# SCH_Controller.net
KiCad netlist of a schematic drawn in Altium Designer
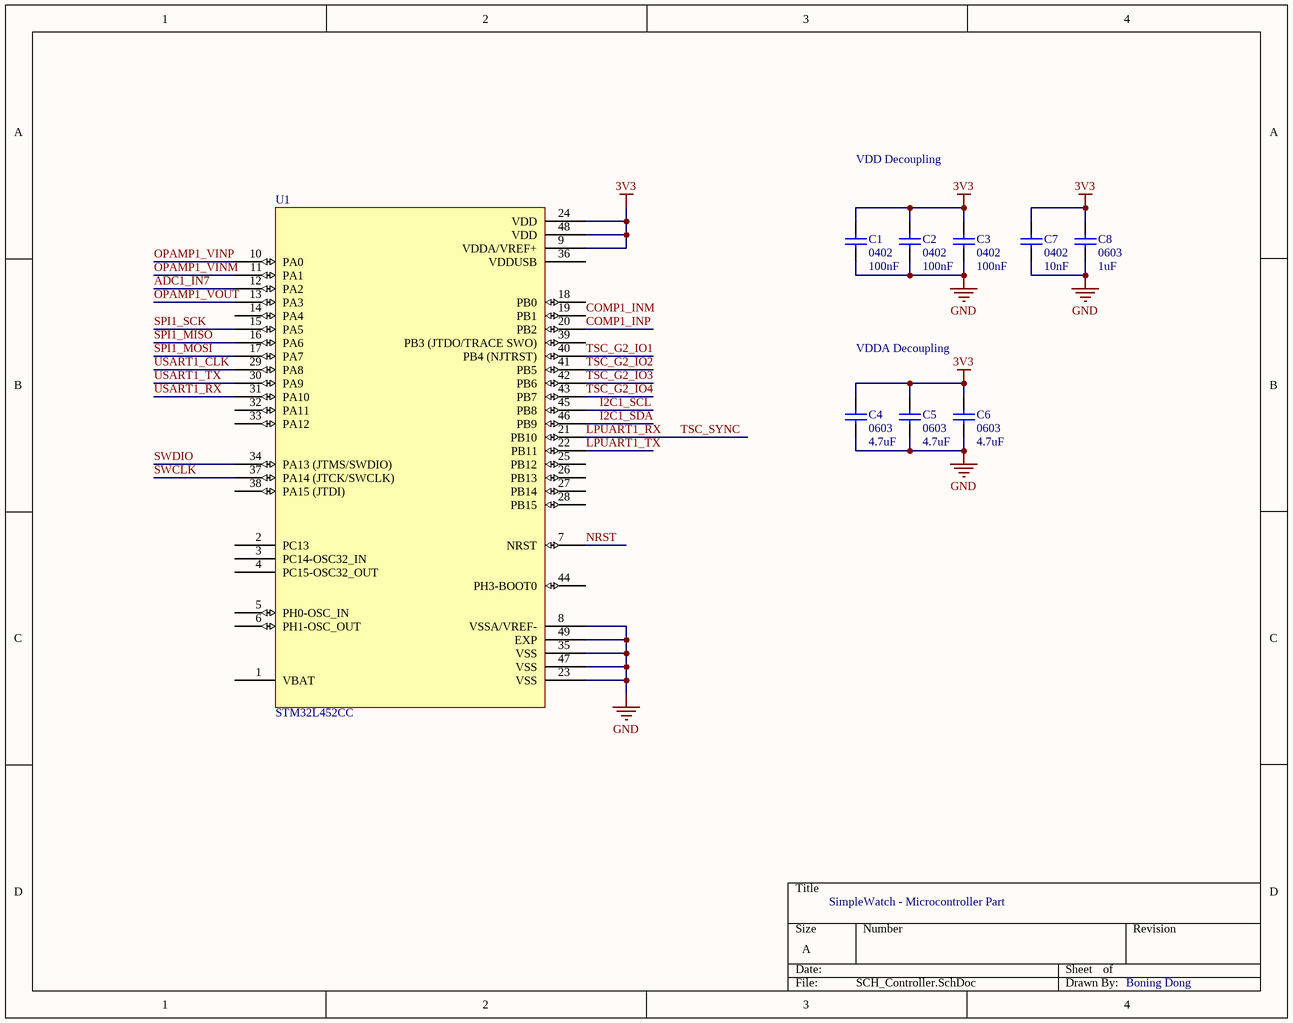
[diagram p0: SCH_Controller.SchDoc]

(export (version "E")
  (design (tool "Eeschema 10.0.6"))
  (components
    (comp (ref "C1")
      (value "0402")
      (footprint "RAD-0.3")
      (description "Capacitor")
      (fields (field (name "ALTIUM_VALUE") "100nF") (field (name "PUBLISHER") "Altium Limited"))
      (libsource (lib "Miscellaneous Devices") (part "Cap"))
    )
    (comp (ref "C2")
      (value "0402")
      (footprint "RAD-0.3")
      (description "Capacitor")
      (fields (field (name "ALTIUM_VALUE") "100nF") (field (name "PUBLISHER") "Altium Limited"))
      (libsource (lib "Miscellaneous Devices") (part "Cap"))
    )
    (comp (ref "C3")
      (value "0402")
      (footprint "RAD-0.3")
      (description "Capacitor")
      (fields (field (name "ALTIUM_VALUE") "100nF") (field (name "PUBLISHER") "Altium Limited"))
      (libsource (lib "Miscellaneous Devices") (part "Cap"))
    )
    (comp (ref "C4")
      (value "0603")
      (footprint "RAD-0.3")
      (description "Capacitor")
      (fields (field (name "ALTIUM_VALUE") "4.7uF") (field (name "PUBLISHER") "Altium Limited"))
      (libsource (lib "Miscellaneous Devices") (part "Cap"))
    )
    (comp (ref "C5")
      (value "0603")
      (footprint "RAD-0.3")
      (description "Capacitor")
      (fields (field (name "ALTIUM_VALUE") "4.7uF") (field (name "PUBLISHER") "Altium Limited"))
      (libsource (lib "Miscellaneous Devices") (part "Cap"))
    )
    (comp (ref "C6")
      (value "0603")
      (footprint "RAD-0.3")
      (description "Capacitor")
      (fields (field (name "ALTIUM_VALUE") "4.7uF") (field (name "PUBLISHER") "Altium Limited"))
      (libsource (lib "Miscellaneous Devices") (part "Cap"))
    )
    (comp (ref "C7")
      (value "0402")
      (footprint "RAD-0.3")
      (description "Capacitor")
      (fields (field (name "ALTIUM_VALUE") "10nF") (field (name "PUBLISHER") "Altium Limited"))
      (libsource (lib "Miscellaneous Devices") (part "Cap"))
    )
    (comp (ref "C8")
      (value "0603")
      (footprint "RAD-0.3")
      (description "Capacitor")
      (fields (field (name "ALTIUM_VALUE") "1uF") (field (name "PUBLISHER") "Altium Limited"))
      (libsource (lib "Miscellaneous Devices") (part "Cap"))
    )
    (comp (ref "U1")
      (value "STM32L452CC")
      (description "ARM® Cortex®-M4 STM32L4 Microcontroller IC 32-Bit 80MHz 512KB (512K x 8) FLASH 48-UFQFPN (7x7)")
      (libsource (lib "Schematic_IC_Micro_Controller") (part "STM32L452CX"))
    )
  )
  (nets
    (net (code "1") (name "/ADC1_IN7") (class "Default")
      (node (ref "U1") (pin "12") (pinfunction "PA2_12") (pintype "bidirectional"))
    )
    (net (code "2") (name "/COMP1_INM") (class "Default")
      (node (ref "U1") (pin "19") (pinfunction "PB1_19") (pintype "bidirectional"))
    )
    (net (code "3") (name "/COMP1_INP") (class "Default")
      (node (ref "U1") (pin "20") (pinfunction "PB2_20") (pintype "bidirectional"))
    )
    (net (code "4") (name "/I2C1_SCL") (class "Default")
      (node (ref "U1") (pin "45") (pinfunction "PB8_45") (pintype "bidirectional"))
    )
    (net (code "5") (name "/I2C1_SDA") (class "Default")
      (node (ref "U1") (pin "46") (pinfunction "PB9_46") (pintype "bidirectional"))
    )
    (net (code "6") (name "/LPUART1_RX") (class "Default")
      (node (ref "U1") (pin "21") (pinfunction "PB10_21") (pintype "bidirectional"))
    )
    (net (code "7") (name "/LPUART1_TX") (class "Default")
      (node (ref "U1") (pin "22") (pinfunction "PB11_22") (pintype "bidirectional"))
    )
    (net (code "8") (name "/NRST") (class "Default")
      (node (ref "U1") (pin "7") (pinfunction "NRST_7") (pintype "bidirectional"))
    )
    (net (code "9") (name "/OPAMP1_VINM") (class "Default")
      (node (ref "U1") (pin "11") (pinfunction "PA1_11") (pintype "bidirectional"))
    )
    (net (code "10") (name "/OPAMP1_VINP") (class "Default")
      (node (ref "U1") (pin "10") (pinfunction "PA0_10") (pintype "bidirectional"))
    )
    (net (code "11") (name "/OPAMP1_VOUT") (class "Default")
      (node (ref "U1") (pin "13") (pinfunction "PA3_13") (pintype "bidirectional"))
    )
    (net (code "12") (name "/SPI1_MISO") (class "Default")
      (node (ref "U1") (pin "16") (pinfunction "PA6_16") (pintype "bidirectional"))
    )
    (net (code "13") (name "/SPI1_MOSI") (class "Default")
      (node (ref "U1") (pin "17") (pinfunction "PA7_17") (pintype "bidirectional"))
    )
    (net (code "14") (name "/SPI1_SCK") (class "Default")
      (node (ref "U1") (pin "15") (pinfunction "PA5_15") (pintype "bidirectional"))
    )
    (net (code "15") (name "/SWCLK") (class "Default")
      (node (ref "U1") (pin "37") (pinfunction "PA14_(JTCK/SWCLK)_37") (pintype "bidirectional"))
    )
    (net (code "16") (name "/SWDIO") (class "Default")
      (node (ref "U1") (pin "34") (pinfunction "PA13_(JTMS/SWDIO)_34") (pintype "bidirectional"))
    )
    (net (code "17") (name "/TSC_G2_IO1") (class "Default")
      (node (ref "U1") (pin "40") (pinfunction "PB4_(NJTRST)_40") (pintype "bidirectional"))
    )
    (net (code "18") (name "/TSC_G2_IO2") (class "Default")
      (node (ref "U1") (pin "41") (pinfunction "PB5_41") (pintype "bidirectional"))
    )
    (net (code "19") (name "/TSC_G2_IO3") (class "Default")
      (node (ref "U1") (pin "42") (pinfunction "PB6_42") (pintype "bidirectional"))
    )
    (net (code "20") (name "/TSC_G2_IO4") (class "Default")
      (node (ref "U1") (pin "43") (pinfunction "PB7_43") (pintype "bidirectional"))
    )
    (net (code "21") (name "/USART1_CLK") (class "Default")
      (node (ref "U1") (pin "29") (pinfunction "PA8_29") (pintype "bidirectional"))
    )
    (net (code "22") (name "/USART1_RX") (class "Default")
      (node (ref "U1") (pin "31") (pinfunction "PA10_31") (pintype "bidirectional"))
    )
    (net (code "23") (name "/USART1_TX") (class "Default")
      (node (ref "U1") (pin "30") (pinfunction "PA9_30") (pintype "bidirectional"))
    )
    (net (code "24") (name "3V3") (class "Default")
      (node (ref "C1") (pin "2") (pinfunction "2_2") (pintype "passive"))
      (node (ref "C2") (pin "2") (pinfunction "2_2") (pintype "passive"))
      (node (ref "C3") (pin "2") (pinfunction "2_2") (pintype "passive"))
      (node (ref "C4") (pin "2") (pinfunction "2_2") (pintype "passive"))
      (node (ref "C5") (pin "2") (pinfunction "2_2") (pintype "passive"))
      (node (ref "C6") (pin "2") (pinfunction "2_2") (pintype "passive"))
      (node (ref "C7") (pin "2") (pinfunction "2_2") (pintype "passive"))
      (node (ref "C8") (pin "2") (pinfunction "2_2") (pintype "passive"))
      (node (ref "U1") (pin "24") (pinfunction "VDD_24") (pintype "passive"))
      (node (ref "U1") (pin "48") (pinfunction "VDD_48") (pintype "passive"))
      (node (ref "U1") (pin "9") (pinfunction "VDDA/VREF+_9") (pintype "passive"))
    )
    (net (code "25") (name "GND") (class "Default")
      (node (ref "C1") (pin "1") (pinfunction "1_1") (pintype "passive"))
      (node (ref "C2") (pin "1") (pinfunction "1_1") (pintype "passive"))
      (node (ref "C3") (pin "1") (pinfunction "1_1") (pintype "passive"))
      (node (ref "C4") (pin "1") (pinfunction "1_1") (pintype "passive"))
      (node (ref "C5") (pin "1") (pinfunction "1_1") (pintype "passive"))
      (node (ref "C6") (pin "1") (pinfunction "1_1") (pintype "passive"))
      (node (ref "C7") (pin "1") (pinfunction "1_1") (pintype "passive"))
      (node (ref "C8") (pin "1") (pinfunction "1_1") (pintype "passive"))
      (node (ref "U1") (pin "23") (pinfunction "VSS_23") (pintype "passive"))
      (node (ref "U1") (pin "35") (pinfunction "VSS_35") (pintype "passive"))
      (node (ref "U1") (pin "47") (pinfunction "VSS_47") (pintype "passive"))
      (node (ref "U1") (pin "49") (pinfunction "EXP_49") (pintype "power_in"))
      (node (ref "U1") (pin "8") (pinfunction "VSSA/VREF-_8") (pintype "passive"))
    )
    (net (code "26") (name "unconnected-(U1-PA4-Pad14)") (class "Default")
      (node (ref "U1") (pin "14") (pinfunction "PA4_14") (pintype "bidirectional"))
    )
    (net (code "27") (name "unconnected-(U1-PA11-Pad32)") (class "Default")
      (node (ref "U1") (pin "32") (pinfunction "PA11_32") (pintype "bidirectional"))
    )
    (net (code "28") (name "unconnected-(U1-PA12-Pad33)") (class "Default")
      (node (ref "U1") (pin "33") (pinfunction "PA12_33") (pintype "bidirectional"))
    )
    (net (code "29") (name "unconnected-(U1-PA15_(JTDI)-Pad38)") (class "Default")
      (node (ref "U1") (pin "38") (pinfunction "PA15_(JTDI)_38") (pintype "bidirectional"))
    )
    (net (code "30") (name "unconnected-(U1-PB0-Pad18)") (class "Default")
      (node (ref "U1") (pin "18") (pinfunction "PB0_18") (pintype "bidirectional"))
    )
    (net (code "31") (name "unconnected-(U1-PB3_(JTDO{slash}TRACE_SWO)-Pad39)") (class "Default")
      (node (ref "U1") (pin "39") (pinfunction "PB3_(JTDO/TRACE_SWO)_39") (pintype "bidirectional"))
    )
    (net (code "32") (name "unconnected-(U1-PB12-Pad25)") (class "Default")
      (node (ref "U1") (pin "25") (pinfunction "PB12_25") (pintype "bidirectional"))
    )
    (net (code "33") (name "unconnected-(U1-PB13-Pad26)") (class "Default")
      (node (ref "U1") (pin "26") (pinfunction "PB13_26") (pintype "bidirectional"))
    )
    (net (code "34") (name "unconnected-(U1-PB14-Pad27)") (class "Default")
      (node (ref "U1") (pin "27") (pinfunction "PB14_27") (pintype "bidirectional"))
    )
    (net (code "35") (name "unconnected-(U1-PB15-Pad28)") (class "Default")
      (node (ref "U1") (pin "28") (pinfunction "PB15_28") (pintype "bidirectional"))
    )
    (net (code "36") (name "unconnected-(U1-PC13-Pad2)") (class "Default")
      (node (ref "U1") (pin "2") (pinfunction "PC13_2") (pintype "passive"))
    )
    (net (code "37") (name "unconnected-(U1-PC14-OSC32_IN-Pad3)") (class "Default")
      (node (ref "U1") (pin "3") (pinfunction "PC14-OSC32_IN_3") (pintype "passive"))
    )
    (net (code "38") (name "unconnected-(U1-PC15-OSC32_OUT-Pad4)") (class "Default")
      (node (ref "U1") (pin "4") (pinfunction "PC15-OSC32_OUT_4") (pintype "passive"))
    )
    (net (code "39") (name "unconnected-(U1-PH0-OSC_IN-Pad5)") (class "Default")
      (node (ref "U1") (pin "5") (pinfunction "PH0-OSC_IN_5") (pintype "bidirectional"))
    )
    (net (code "40") (name "unconnected-(U1-PH1-OSC_OUT-Pad6)") (class "Default")
      (node (ref "U1") (pin "6") (pinfunction "PH1-OSC_OUT_6") (pintype "bidirectional"))
    )
    (net (code "41") (name "unconnected-(U1-PH3-BOOT0-Pad44)") (class "Default")
      (node (ref "U1") (pin "44") (pinfunction "PH3-BOOT0_44") (pintype "bidirectional"))
    )
    (net (code "42") (name "unconnected-(U1-VBAT-Pad1)") (class "Default")
      (node (ref "U1") (pin "1") (pinfunction "VBAT_1") (pintype "passive"))
    )
    (net (code "43") (name "unconnected-(U1-VDDUSB-Pad36)") (class "Default")
      (node (ref "U1") (pin "36") (pinfunction "VDDUSB_36") (pintype "passive"))
    )
  )
)
